# ElectronicSpeedController.net
KiCad netlist of a schematic drawn in Altium Designer
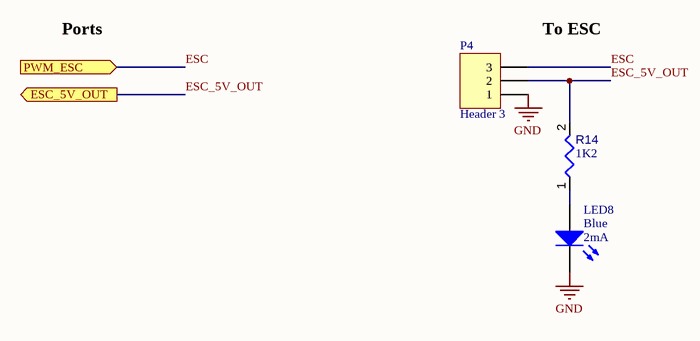
[diagram p0: ElectronicSpeedController.SchDoc]

(export (version "E")
  (design (tool "Eeschema 10.0.6"))
  (components
    (comp (ref "LED8")
      (value "Blue")
      (footprint "1206_A")
      (description "KPT-3216LVVBC-D -  LED, 3.2mm x 1.6mm, Blue, SMD, 2 mA, 2.65 V, 470 nm")
      (fields
        (field (name "MANUFACTURER") "Kingbright")
        (field (name "PARTNUMBER") "KPT-3216LVVBC-D")
        (field (name "IF") "2mA")
      )
      (libsource (lib "Altium Content Vault") (part "CMP-1426-00015-1"))
    )
    (comp (ref "P4")
      (value "Header 3")
      (footprint "HDR1X3")
      (description "Header, 3-Pin")
      (fields (field (name "PUBLISHER") "Altium Limited"))
      (libsource (lib "Miscellaneous Connectors") (part "Header 3"))
    )
    (comp (ref "R14")
      (value "1K2")
      (footprint "RESC0805(2012)_L")
      (description "1K2 0.125W 5% 0805 (2012 Metric)  SMD")
      (fields (field (name "POWER") "0.125W") (field (name "TOLERANCE") "5%"))
      (libsource (lib "James Cook University") (part "1KR5J"))
    )
  )
  (nets
    (net (code "1") (name "/ESC") (class "Default")
      (node (ref "P4") (pin "3") (pinfunction "3_3") (pintype "passive"))
    )
    (net (code "2") (name "/ESC_5V_OUT") (class "Default")
      (node (ref "P4") (pin "2") (pinfunction "2_2") (pintype "passive"))
      (node (ref "R14") (pin "2") (pinfunction "2_2") (pintype "passive"))
    )
    (net (code "3") (name "GND") (class "Default")
      (node (ref "LED8") (pin "1") (pinfunction "K_1") (pintype "passive"))
      (node (ref "P4") (pin "1") (pinfunction "1_1") (pintype "passive"))
    )
    (net (code "4") (name "Net-(LED8-A)") (class "Default")
      (node (ref "LED8") (pin "2") (pinfunction "A_2") (pintype "passive"))
      (node (ref "R14") (pin "1") (pinfunction "1_1") (pintype "passive"))
    )
  )
)
